# Audio_Module.net
KiCad netlist of a schematic drawn in Altium Designer
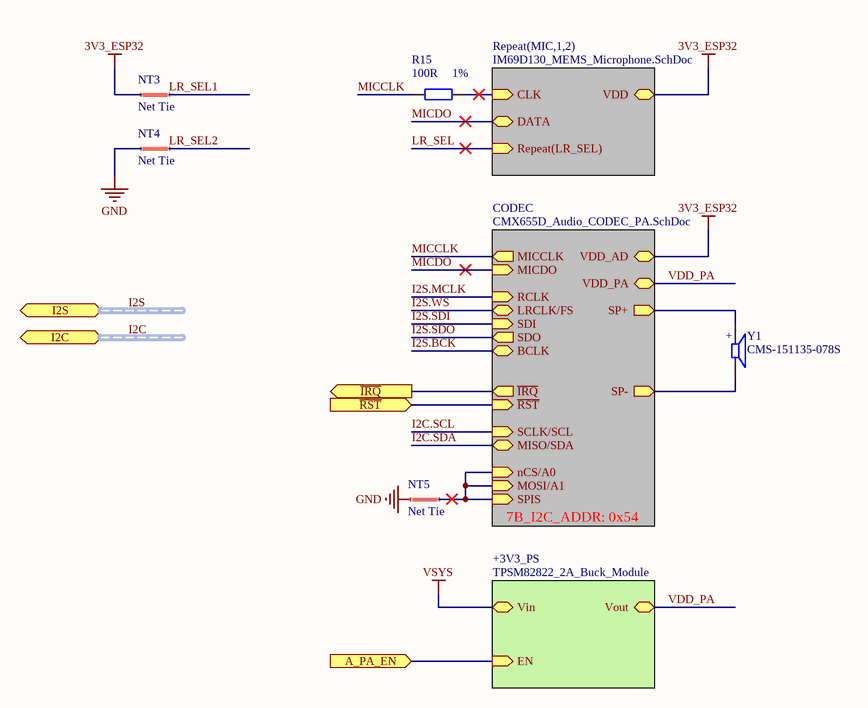
[diagram p0: Audio_Module.SchDoc]

(export (version "E")
  (design (tool "Eeschema 10.0.6"))
  (components
    (comp (ref "NT3")
      (value "Net Tie")
      (footprint "Net Tie 6x30mil")
      (libsource (lib "BLDC_Motor_Driver") (part "Net Tie Line"))
    )
    (comp (ref "NT4")
      (value "Net Tie")
      (footprint "Net Tie 6x30mil")
      (libsource (lib "BLDC_Motor_Driver") (part "Net Tie Line"))
    )
    (comp (ref "NT5")
      (value "Net Tie")
      (footprint "Net Tie 6x30mil")
      (libsource (lib "BLDC_Motor_Driver") (part "Net Tie Line"))
    )
    (comp (ref "R15")
      (value "RES SMD 100 OHM 1% 1/16W 0402")
      (footprint "0402R")
      (description "100 Ohms ±1% 0.063W, 1/16W Chip Resistor 0402 (1005 Metric) Moisture Resistant Thick Film")
      (fields
        (field (name "MANUFACTURER") "Yageo")
        (field (name "MANUFACTURER PART NUMBER") "RC0402FR-07100RL")
        (field (name "TOLERANCE") "1%")
        (field (name "RESISTANCE") "100R")
      )
      (libsource (lib "resistors_smd") (part "RES SMD 100 OHM 1% 1/16W 0402"))
    )
    (comp (ref "Y1")
      (value "CMS-151135-078S")
      (footprint "SPKR_CMS-151135-078S")
      (description "8 Ohms General Purpose Speaker 700mW 100Hz ~ 20kHz Top Rectangular")
      (fields (field (name "MANUFACTURER") "CUI"))
      (libsource (lib "BLDC_Motor_Driver") (part "SPEAKER CMS-151135-078S 15 X 11 MM ENCLOSED"))
    )
  )
  (nets
    (net (code "4") (name "/CLK") (class "Default")
      (node (ref "R15") (pin "1") (pinfunction "1_1") (pintype "passive"))
    )
    (net (code "14") (name "/LR_SEL1") (class "Default") (node (ref "NT3") (pin "2") (pintype "passive")))
    (net (code "15") (name "/LR_SEL2") (class "Default") (node (ref "NT4") (pin "2") (pintype "passive")))
    (net (code "16") (name "/MICCLK") (class "Default")
      (node (ref "R15") (pin "2") (pinfunction "2_2") (pintype "passive"))
    )
    (net (code "18") (name "/MOSI{slash}A1") (class "Default")
      (node (ref "NT5") (pin "2") (pintype "passive"))
    )
    (net (code "20") (name "/SP+") (class "Default")
      (node (ref "Y1") (pin "P") (pinfunction "1_P") (pintype "passive"))
    )
    (net (code "21") (name "/SP-") (class "Default")
      (node (ref "Y1") (pin "M") (pinfunction "2_M") (pintype "passive"))
    )
    (net (code "25") (name "3V3_ESP32") (class "Default") (node (ref "NT3") (pin "1") (pintype "passive")))
    (net (code "26") (name "GND") (class "Default")
      (node (ref "NT4") (pin "1") (pintype "passive"))
      (node (ref "NT5") (pin "1") (pintype "passive"))
    )
  )
)
